# mcp2221_tssop.net
KiCad netlist of a schematic drawn in EAGLE
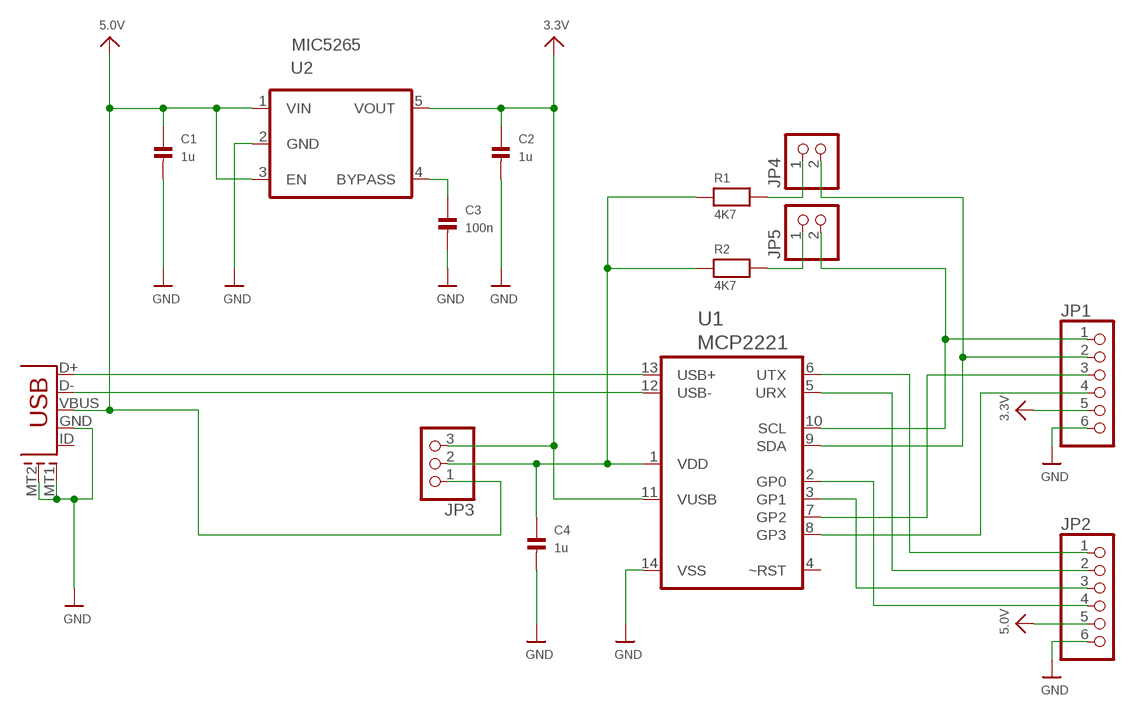
[diagram p0: schematic, sheet 1]

(export (version "E")
  (design (tool "Eeschema 10.0.6"))
  (components
    (comp (ref "C1")
      (value "1u")
      (footprint "eagle-import:0805")
      (libsource (lib "eagle-import") (part "CAP_CERAMIC0805"))
    )
    (comp (ref "C2")
      (value "1u")
      (footprint "eagle-import:0805")
      (libsource (lib "eagle-import") (part "CAP_CERAMIC0805"))
    )
    (comp (ref "C3")
      (value "100n")
      (footprint "eagle-import:0805")
      (libsource (lib "eagle-import") (part "CAP_CERAMIC0805"))
    )
    (comp (ref "C4")
      (value "1u")
      (footprint "eagle-import:0805")
      (libsource (lib "eagle-import") (part "CAP_CERAMIC0805"))
    )
    (comp (ref "JP1")
      (value "PINHD-1X6")
      (footprint "eagle-import:1X06")
      (libsource (lib "eagle-import") (part "PINHD-1X6"))
    )
    (comp (ref "JP2")
      (value "PINHD-1X6")
      (footprint "eagle-import:1X06")
      (libsource (lib "eagle-import") (part "PINHD-1X6"))
    )
    (comp (ref "JP3")
      (value "PINHD-1X3")
      (footprint "eagle-import:1X03")
      (libsource (lib "eagle-import") (part "PINHD-1X3"))
    )
    (comp (ref "JP4")
      (value "PINHD-1X2")
      (footprint "eagle-import:1X02")
      (libsource (lib "eagle-import") (part "PINHD-1X2"))
    )
    (comp (ref "JP5")
      (value "PINHD-1X2")
      (footprint "eagle-import:1X02")
      (libsource (lib "eagle-import") (part "PINHD-1X2"))
    )
    (comp (ref "R1")
      (value "4K7")
      (footprint "eagle-import:0805")
      (libsource (lib "eagle-import") (part "RESISTOR0805"))
    )
    (comp (ref "R2")
      (value "4K7")
      (footprint "eagle-import:0805")
      (libsource (lib "eagle-import") (part "RESISTOR0805"))
    )
    (comp (ref "U1")
      (value "MCP2221")
      (footprint "eagle-import:TSSOP14")
      (libsource (lib "eagle-import") (part "MCP2221TSSOP"))
    )
    (comp (ref "U2")
      (value "MIC5265")
      (footprint "eagle-import:SOT95P275X110-5N")
      (libsource (lib "eagle-import") (part "REGULATOR_5"))
    )
    (comp (ref "USB1")
      (value "USB-MICROBLARGEPAD")
      (footprint "eagle-import:USB-MICROB_LARGEPAD")
      (libsource (lib "eagle-import") (part "USB-MICROBLARGEPAD"))
    )
  )
  (nets
    (net (code "1") (name "3.3V") (class "Default")
      (node (ref "C2") (pin "1") (pinfunction "P$1_1") (pintype "passive"))
      (node (ref "JP1") (pin "5") (pinfunction "5_5") (pintype "passive"))
      (node (ref "JP3") (pin "3") (pinfunction "3_3") (pintype "passive"))
      (node (ref "U1") (pin "11") (pinfunction "VUSB_11") (pintype "input"))
      (node (ref "U2") (pin "5") (pinfunction "VOUT_5") (pintype "output"))
    )
    (net (code "2") (name "5.0V") (class "Default")
      (node (ref "C1") (pin "1") (pinfunction "P$1_1") (pintype "passive"))
      (node (ref "JP2") (pin "5") (pinfunction "5_5") (pintype "passive"))
      (node (ref "JP3") (pin "1") (pinfunction "1_1") (pintype "passive"))
      (node (ref "U2") (pin "1") (pinfunction "VIN_1") (pintype "power_in"))
      (node (ref "U2") (pin "3") (pinfunction "EN_3") (pintype "input"))
      (node (ref "USB1") (pin "VBUS") (pinfunction "VBUS_VBUS") (pintype "bidirectional"))
    )
    (net (code "3") (name "GND") (class "Default")
      (node (ref "C1") (pin "2") (pinfunction "P$2_2") (pintype "passive"))
      (node (ref "C2") (pin "2") (pinfunction "P$2_2") (pintype "passive"))
      (node (ref "C3") (pin "2") (pinfunction "P$2_2") (pintype "passive"))
      (node (ref "C4") (pin "2") (pinfunction "P$2_2") (pintype "passive"))
      (node (ref "JP1") (pin "6") (pinfunction "6_6") (pintype "passive"))
      (node (ref "JP2") (pin "6") (pinfunction "6_6") (pintype "passive"))
      (node (ref "U1") (pin "14") (pinfunction "VSS_14") (pintype "passive"))
      (node (ref "U2") (pin "2") (pinfunction "GND_2") (pintype "passive"))
      (node (ref "USB1") (pin "GND") (pinfunction "GND_GND") (pintype "bidirectional"))
      (node (ref "USB1") (pin "MT1") (pinfunction "SHEILD1_MT1") (pintype "bidirectional"))
      (node (ref "USB1") (pin "MT2") (pinfunction "SHEILD2_MT2") (pintype "bidirectional"))
    )
    (net (code "4") (name "Net-(C3-P$1)") (class "Default")
      (node (ref "C3") (pin "1") (pinfunction "P$1_1") (pintype "passive"))
      (node (ref "U2") (pin "4") (pinfunction "BYPASS_4") (pintype "passive"))
    )
    (net (code "5") (name "Net-(C4-P$1)") (class "Default")
      (node (ref "C4") (pin "1") (pinfunction "P$1_1") (pintype "passive"))
      (node (ref "JP3") (pin "2") (pinfunction "2_2") (pintype "passive"))
      (node (ref "R1") (pin "1") (pinfunction "1_1") (pintype "passive"))
      (node (ref "R2") (pin "1") (pinfunction "1_1") (pintype "passive"))
      (node (ref "U1") (pin "1") (pinfunction "VDD_1") (pintype "passive"))
    )
    (net (code "6") (name "Net-(JP4-Pad1)") (class "Default")
      (node (ref "JP4") (pin "1") (pinfunction "1_1") (pintype "passive"))
      (node (ref "R1") (pin "2") (pinfunction "2_2") (pintype "passive"))
    )
    (net (code "7") (name "Net-(JP5-Pad1)") (class "Default")
      (node (ref "JP5") (pin "1") (pinfunction "1_1") (pintype "passive"))
      (node (ref "R2") (pin "2") (pinfunction "2_2") (pintype "passive"))
    )
    (net (code "8") (name "Net-(U1-GP0)") (class "Default")
      (node (ref "JP2") (pin "4") (pinfunction "4_4") (pintype "passive"))
      (node (ref "U1") (pin "2") (pinfunction "GP0_2") (pintype "output"))
    )
    (net (code "9") (name "Net-(U1-GP1)") (class "Default")
      (node (ref "JP2") (pin "3") (pinfunction "3_3") (pintype "passive"))
      (node (ref "U1") (pin "3") (pinfunction "GP1_3") (pintype "output"))
    )
    (net (code "10") (name "Net-(U1-GP2)") (class "Default")
      (node (ref "JP1") (pin "3") (pinfunction "3_3") (pintype "passive"))
      (node (ref "U1") (pin "7") (pinfunction "GP2_7") (pintype "output"))
    )
    (net (code "11") (name "Net-(U1-GP3)") (class "Default")
      (node (ref "JP1") (pin "4") (pinfunction "4_4") (pintype "passive"))
      (node (ref "U1") (pin "8") (pinfunction "GP3_8") (pintype "output"))
    )
    (net (code "12") (name "Net-(U1-SCL)") (class "Default")
      (node (ref "JP1") (pin "1") (pinfunction "1_1") (pintype "passive"))
      (node (ref "JP5") (pin "2") (pinfunction "2_2") (pintype "passive"))
      (node (ref "U1") (pin "10") (pinfunction "SCL_10") (pintype "output"))
    )
    (net (code "13") (name "Net-(U1-SDA)") (class "Default")
      (node (ref "JP1") (pin "2") (pinfunction "2_2") (pintype "passive"))
      (node (ref "JP4") (pin "2") (pinfunction "2_2") (pintype "passive"))
      (node (ref "U1") (pin "9") (pinfunction "SDA_9") (pintype "output"))
    )
    (net (code "14") (name "Net-(U1-URX)") (class "Default")
      (node (ref "JP2") (pin "2") (pinfunction "2_2") (pintype "passive"))
      (node (ref "U1") (pin "5") (pinfunction "URX_5") (pintype "output"))
    )
    (net (code "15") (name "Net-(U1-USB+)") (class "Default")
      (node (ref "U1") (pin "13") (pinfunction "USB+_13") (pintype "passive"))
      (node (ref "USB1") (pin "D+") (pinfunction "D+_D+") (pintype "bidirectional"))
    )
    (net (code "16") (name "Net-(U1-USB-)") (class "Default")
      (node (ref "U1") (pin "12") (pinfunction "USB-_12") (pintype "passive"))
      (node (ref "USB1") (pin "D-") (pinfunction "D-_D-") (pintype "bidirectional"))
    )
    (net (code "17") (name "Net-(U1-UTX)") (class "Default")
      (node (ref "JP2") (pin "1") (pinfunction "1_1") (pintype "passive"))
      (node (ref "U1") (pin "6") (pinfunction "UTX_6") (pintype "output"))
    )
    (net (code "18") (name "unconnected-(U1-~{RST}-Pad4)") (class "Default")
      (node (ref "U1") (pin "4") (pinfunction "~{RST}_4") (pintype "output"))
    )
    (net (code "19") (name "unconnected-(USB1-PadID)") (class "Default")
      (node (ref "USB1") (pin "ID") (pinfunction "ID_ID") (pintype "bidirectional"))
    )
  )
)
